# Driving__Circuit.net
KiCad netlist of a schematic drawn in Altium Designer
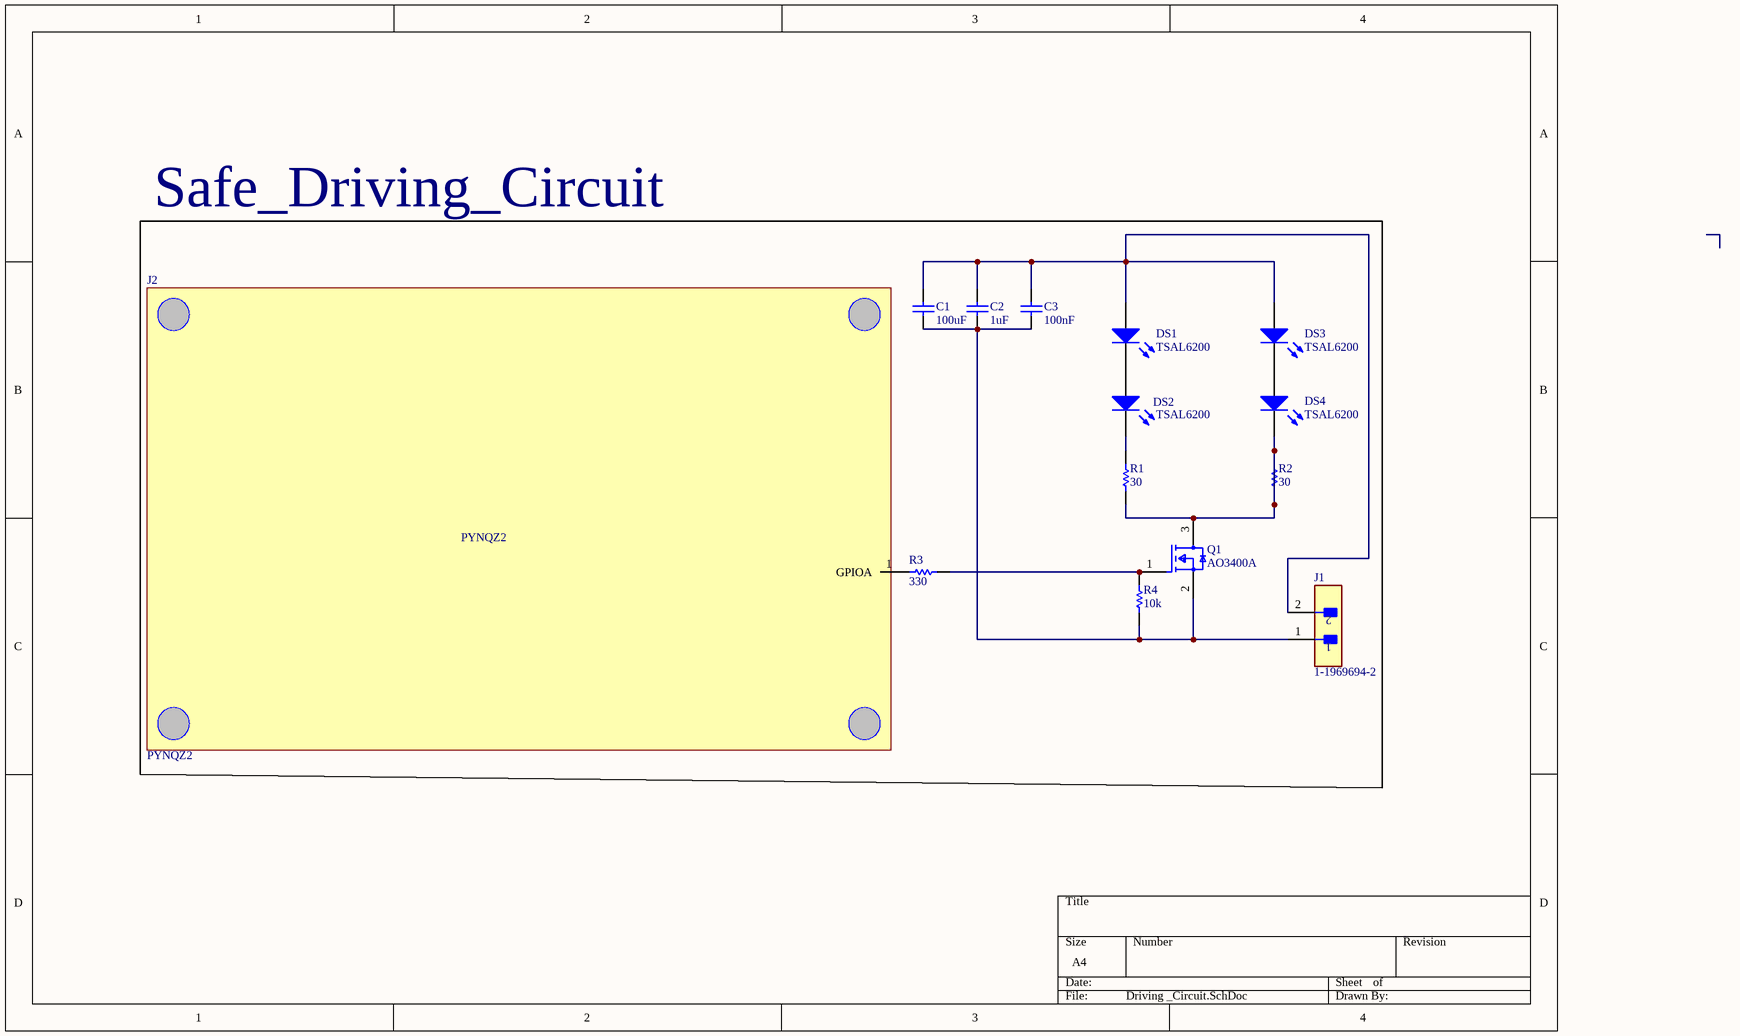
[diagram p0: Driving _Circuit.SchDoc]

(export (version "E")
  (design (tool "Eeschema 10.0.6"))
  (components
    (comp (ref "C1")
      (value "100uF")
      (footprint "CAPC2013X145X48ML20T23")
      (fields (field (name "MANUFACTURER") "Vitramon") (field (name "PART NUMBER") "VJ0805Y682KXAMT"))
      (libsource (lib "Altium Content Vault") (part "CAP"))
    )
    (comp (ref "C2")
      (value "1uF")
      (footprint "CAPC2013X145X48ML20T23")
      (fields (field (name "MANUFACTURER") "Vitramon") (field (name "PART NUMBER") "VJ0805Y682KXAMT"))
      (libsource (lib "Altium Content Vault") (part "CAP"))
    )
    (comp (ref "C3")
      (value "100nF")
      (footprint "CAPC2013X145X48ML20T23")
      (fields (field (name "MANUFACTURER") "Vitramon") (field (name "PART NUMBER") "VJ0805Y682KXAMT"))
      (libsource (lib "Altium Content Vault") (part "CAP"))
    )
    (comp (ref "DS1")
      (value "TSAL6200")
      (footprint "VISH-TSAL6200")
      (fields (field (name "MANUFACTURER") "Vishay"))
      (libsource (lib "Altium Content Vault") (part "LED-AK-2"))
    )
    (comp (ref "DS2")
      (value "TSAL6200")
      (footprint "VISH-TSAL6200")
      (fields (field (name "MANUFACTURER") "Vishay"))
      (libsource (lib "Altium Content Vault") (part "LED-AK-2"))
    )
    (comp (ref "DS3")
      (value "TSAL6200")
      (footprint "VISH-TSAL6200")
      (fields (field (name "MANUFACTURER") "Vishay"))
      (libsource (lib "Altium Content Vault") (part "LED-AK-2"))
    )
    (comp (ref "DS4")
      (value "TSAL6200")
      (footprint "VISH-TSAL6200")
      (fields (field (name "MANUFACTURER") "Vishay"))
      (libsource (lib "Altium Content Vault") (part "LED-AK-2"))
    )
    (comp (ref "J1")
      (value "1-1969694-2")
      (footprint "FP-1-1969694-2-MFG")
      (description "CONN HEADER R/A 2POS 6MM")
      (libsource (lib "Altium Content Vault") (part "3bc925449376181038e59eaffc5286c"))
    )
    (comp (ref "J2") (value "PYNQZ2") (footprint "PYNQZ2_board") (libsource (lib "Schlib1") (part "PYNQZ2")))
    (comp (ref "Q1")
      (value "AO3400A")
      (footprint "FP-SOT23-MFG")
      (description "MOSFET N-CH 30V 5.7A SOT23")
      (libsource (lib "Altium Content Vault") (part "0a9ea7c96deaaede766a5b531c28de0"))
    )
    (comp (ref "R1")
      (value "30")
      (footprint "RESC3116X65X40LL10T20")
      (fields (field (name "PART NUMBER") "RC1206FR-10750RL") (field (name "MANUFACTURER") "Yageo"))
      (libsource (lib "Altium Content Vault") (part "RES"))
    )
    (comp (ref "R2")
      (value "30")
      (footprint "RESC3116X65X40LL10T20")
      (fields (field (name "PART NUMBER") "RC1206FR-10750RL") (field (name "MANUFACTURER") "Yageo"))
      (libsource (lib "Altium Content Vault") (part "RES"))
    )
    (comp (ref "R3")
      (value "330")
      (footprint "RESC3116X65X40LL10T20")
      (fields (field (name "PART NUMBER") "RC1206FR-10750RL") (field (name "MANUFACTURER") "Yageo"))
      (libsource (lib "Altium Content Vault") (part "RES"))
    )
    (comp (ref "R4")
      (value "10k")
      (footprint "RESC3116X65X40LL10T20")
      (fields (field (name "PART NUMBER") "RC1206FR-10750RL") (field (name "MANUFACTURER") "Yageo"))
      (libsource (lib "Altium Content Vault") (part "RES"))
    )
  )
  (nets
    (net (code "1") (name "Net-(DS1-A)") (class "Default")
      (node (ref "C1") (pin "2") (pinfunction "2_2") (pintype "passive"))
      (node (ref "C2") (pin "2") (pinfunction "2_2") (pintype "passive"))
      (node (ref "C3") (pin "2") (pinfunction "2_2") (pintype "passive"))
      (node (ref "DS1") (pin "1") (pinfunction "A_1") (pintype "passive"))
      (node (ref "DS3") (pin "1") (pinfunction "A_1") (pintype "passive"))
      (node (ref "J1") (pin "2") (pinfunction "2_2") (pintype "passive"))
    )
    (net (code "2") (name "Net-(DS1-K)") (class "Default")
      (node (ref "DS1") (pin "2") (pinfunction "K_2") (pintype "passive"))
      (node (ref "DS2") (pin "1") (pinfunction "A_1") (pintype "passive"))
    )
    (net (code "3") (name "Net-(DS2-K)") (class "Default")
      (node (ref "DS2") (pin "2") (pinfunction "K_2") (pintype "passive"))
      (node (ref "R1") (pin "2") (pinfunction "2_2") (pintype "passive"))
    )
    (net (code "4") (name "Net-(DS3-K)") (class "Default")
      (node (ref "DS3") (pin "2") (pinfunction "K_2") (pintype "passive"))
      (node (ref "DS4") (pin "1") (pinfunction "A_1") (pintype "passive"))
    )
    (net (code "5") (name "Net-(DS4-K)") (class "Default")
      (node (ref "DS4") (pin "2") (pinfunction "K_2") (pintype "passive"))
      (node (ref "Q1") (pin "3") (pinfunction "D_3") (pintype "passive"))
      (node (ref "R1") (pin "1") (pinfunction "1_1") (pintype "passive"))
      (node (ref "R2") (pin "1") (pinfunction "1_1") (pintype "passive"))
      (node (ref "R2") (pin "2") (pinfunction "2_2") (pintype "passive"))
    )
    (net (code "6") (name "Net-(J2-GPIOA)") (class "Default")
      (node (ref "J2") (pin "1") (pinfunction "GPIOA_1") (pintype "passive"))
      (node (ref "R3") (pin "2") (pinfunction "2_2") (pintype "passive"))
    )
    (net (code "7") (name "Net-(Q1-G)") (class "Default")
      (node (ref "Q1") (pin "1") (pinfunction "G_1") (pintype "passive"))
      (node (ref "R3") (pin "1") (pinfunction "1_1") (pintype "passive"))
      (node (ref "R4") (pin "2") (pinfunction "2_2") (pintype "passive"))
    )
    (net (code "8") (name "Net-(Q1-S)") (class "Default")
      (node (ref "C1") (pin "1") (pinfunction "1_1") (pintype "passive"))
      (node (ref "C2") (pin "1") (pinfunction "1_1") (pintype "passive"))
      (node (ref "C3") (pin "1") (pinfunction "1_1") (pintype "passive"))
      (node (ref "J1") (pin "1") (pinfunction "1_1") (pintype "passive"))
      (node (ref "Q1") (pin "2") (pinfunction "S_2") (pintype "passive"))
      (node (ref "R4") (pin "1") (pinfunction "1_1") (pintype "passive"))
    )
  )
)
